# Condor2a_Herlink.net
KiCad netlist of a schematic drawn in Altium Designer
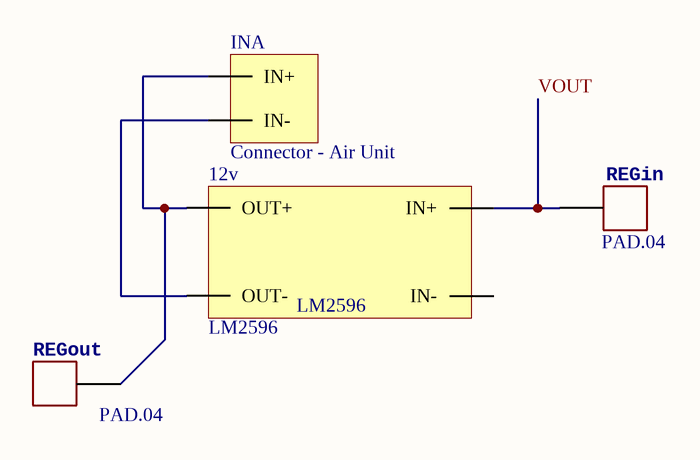
[diagram p0: Condor2a_Herlink.SchDoc]

(export (version "E")
  (design (tool "Eeschema 10.0.6"))
  (components
    (comp (ref "12v")
      (value "LM2596")
      (footprint "LM2596 DC-DC HW-411")
      (libsource (lib "CB_REV_C") (part "LM2596"))
    )
    (comp (ref "INA")
      (value "Connector - Air Unit")
      (footprint "Connector - Air Unir")
      (libsource (lib "CB_REV_C") (part "Connector - Air Unit"))
    )
    (comp (ref "REGin")
      (value "PAD.04")
      (footprint "PAD.04X.04")
      (libsource (lib "CB_REV_C") (part "PAD.04"))
    )
    (comp (ref "REGout")
      (value "PAD.04")
      (footprint "PAD.04X.04")
      (libsource (lib "CB_REV_C") (part "PAD.04"))
    )
  )
  (nets
    (net (code "1") (name "/VOUT") (class "Default")
      (node (ref "12v") (pin "IN+") (pinfunction "IN+_IN+") (pintype "passive"))
      (node (ref "REGin") (pin "P$1") (pinfunction "P$1_P$1") (pintype "passive"))
    )
    (net (code "2") (name "Net-(INA-IN+)") (class "Default")
      (node (ref "12v") (pin "OUT+") (pinfunction "OUT+_OUT+") (pintype "passive"))
      (node (ref "INA") (pin "1") (pinfunction "IN+_1") (pintype "passive"))
      (node (ref "REGout") (pin "P$1") (pinfunction "P$1_P$1") (pintype "passive"))
    )
    (net (code "3") (name "Net-(INA-IN-)") (class "Default")
      (node (ref "12v") (pin "OUT-") (pinfunction "OUT-_OUT-") (pintype "passive"))
      (node (ref "INA") (pin "2") (pinfunction "IN-_2") (pintype "passive"))
    )
    (net (code "4") (name "unconnected-(12v-PadIN-)") (class "Default")
      (node (ref "12v") (pin "IN-") (pinfunction "IN-_IN-") (pintype "passive"))
    )
  )
)
